# interface_a.net
KiCad netlist of a schematic drawn in EAGLE
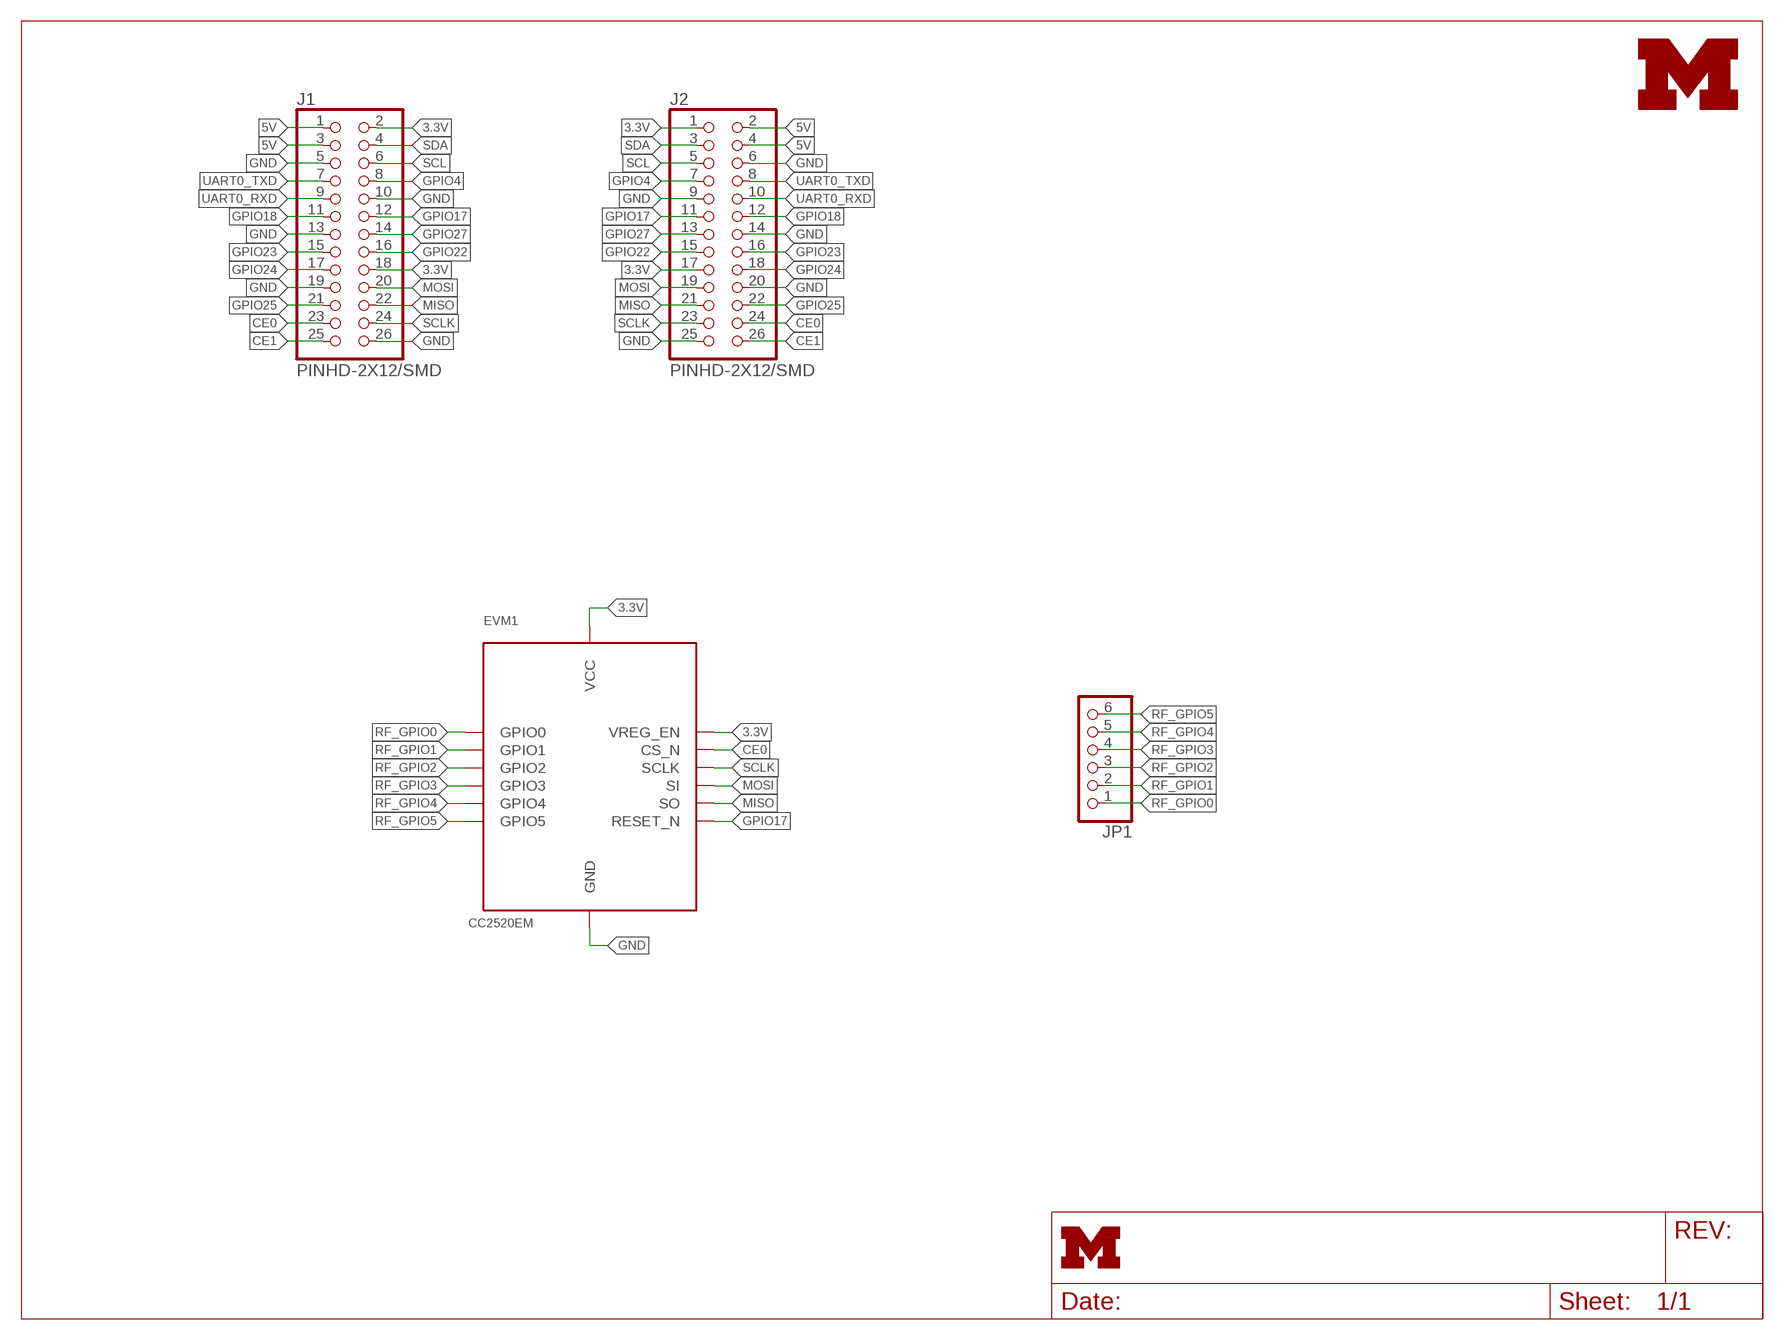
[diagram p0: schematic, sheet 1]

(export (version "E")
  (design (tool "Eeschema 10.0.6"))
  (components
    (comp (ref "EVM1")
      (value "CC2520EM")
      (footprint "eagle-import:TI_CC_EVM")
      (libsource (lib "eagle-import") (part "CC2520EM"))
    )
    (comp (ref "J1")
      (value "PINHD-2X12/SMD")
      (footprint "eagle-import:2X13_SMD")
      (libsource (lib "eagle-import") (part "PINHD-2X12/SMD"))
    )
    (comp (ref "J2")
      (value "PINHD-2X12/SMD")
      (footprint "eagle-import:2X13_SMD")
      (libsource (lib "eagle-import") (part "PINHD-2X12/SMD"))
    )
    (comp (ref "JP1")
      (value "PINHD-1X6/90")
      (footprint "eagle-import:1X06_90")
      (libsource (lib "eagle-import") (part "PINHD-1X6/90"))
    )
    (comp (ref "U$1")
      (value "UMICH_SOLID_SMALL")
      (footprint "eagle-import:UMICH_SOLID_75MIL")
      (libsource (lib "eagle-import") (part "UMICH_SOLID_SMALL"))
    )
  )
  (nets
    (net (code "1") (name "3.3V") (class "Default")
      (node (ref "EVM1") (pin "P1_10") (pinfunction "VREG_EN_P1_10") (pintype "bidirectional"))
      (node (ref "EVM1") (pin "P2_7") (pinfunction "VCC_P2_7") (pintype "bidirectional"))
      (node (ref "EVM1") (pin "P2_9") (pinfunction "VCC_P2_9") (pintype "bidirectional"))
      (node (ref "J1") (pin "18") (pinfunction "18_18") (pintype "passive"))
      (node (ref "J1") (pin "2") (pinfunction "2_2") (pintype "passive"))
      (node (ref "J2") (pin "1") (pinfunction "1_1") (pintype "passive"))
      (node (ref "J2") (pin "17") (pinfunction "17_17") (pintype "passive"))
    )
    (net (code "2") (name "5V") (class "Default")
      (node (ref "J1") (pin "1") (pinfunction "1_1") (pintype "passive"))
      (node (ref "J1") (pin "3") (pinfunction "3_3") (pintype "passive"))
      (node (ref "J2") (pin "2") (pinfunction "2_2") (pintype "passive"))
      (node (ref "J2") (pin "4") (pinfunction "4_4") (pintype "passive"))
    )
    (net (code "3") (name "CE0") (class "Default")
      (node (ref "EVM1") (pin "P1_14") (pinfunction "CS_N_P1_14") (pintype "bidirectional"))
      (node (ref "J1") (pin "23") (pinfunction "23_23") (pintype "passive"))
      (node (ref "J2") (pin "24") (pinfunction "24_24") (pintype "passive"))
    )
    (net (code "4") (name "CE1") (class "Default")
      (node (ref "J1") (pin "25") (pinfunction "25_25") (pintype "passive"))
      (node (ref "J2") (pin "26") (pinfunction "26_26") (pintype "passive"))
    )
    (net (code "5") (name "GND") (class "Default")
      (node (ref "EVM1") (pin "P1_1") (pinfunction "GND_P1_1") (pintype "bidirectional"))
      (node (ref "EVM1") (pin "P1_19") (pinfunction "GND_P1_19") (pintype "bidirectional"))
      (node (ref "J1") (pin "10") (pinfunction "10_10") (pintype "passive"))
      (node (ref "J1") (pin "13") (pinfunction "13_13") (pintype "passive"))
      (node (ref "J1") (pin "19") (pinfunction "19_19") (pintype "passive"))
      (node (ref "J1") (pin "26") (pinfunction "26_26") (pintype "passive"))
      (node (ref "J1") (pin "5") (pinfunction "5_5") (pintype "passive"))
      (node (ref "J2") (pin "14") (pinfunction "14_14") (pintype "passive"))
      (node (ref "J2") (pin "20") (pinfunction "20_20") (pintype "passive"))
      (node (ref "J2") (pin "25") (pinfunction "25_25") (pintype "passive"))
      (node (ref "J2") (pin "6") (pinfunction "6_6") (pintype "passive"))
      (node (ref "J2") (pin "9") (pinfunction "9_9") (pintype "passive"))
    )
    (net (code "6") (name "GPIO4") (class "Default")
      (node (ref "J1") (pin "8") (pinfunction "8_8") (pintype "passive"))
      (node (ref "J2") (pin "7") (pinfunction "7_7") (pintype "passive"))
    )
    (net (code "7") (name "GPIO17") (class "Default")
      (node (ref "EVM1") (pin "P2_15") (pinfunction "RESET_N_P2_15") (pintype "bidirectional"))
      (node (ref "J1") (pin "12") (pinfunction "12_12") (pintype "passive"))
      (node (ref "J2") (pin "11") (pinfunction "11_11") (pintype "passive"))
    )
    (net (code "8") (name "GPIO18") (class "Default")
      (node (ref "J1") (pin "11") (pinfunction "11_11") (pintype "passive"))
      (node (ref "J2") (pin "12") (pinfunction "12_12") (pintype "passive"))
    )
    (net (code "9") (name "GPIO22") (class "Default")
      (node (ref "J1") (pin "16") (pinfunction "16_16") (pintype "passive"))
      (node (ref "J2") (pin "15") (pinfunction "15_15") (pintype "passive"))
    )
    (net (code "10") (name "GPIO23") (class "Default")
      (node (ref "J1") (pin "15") (pinfunction "15_15") (pintype "passive"))
      (node (ref "J2") (pin "16") (pinfunction "16_16") (pintype "passive"))
    )
    (net (code "11") (name "GPIO24") (class "Default")
      (node (ref "J1") (pin "17") (pinfunction "17_17") (pintype "passive"))
      (node (ref "J2") (pin "18") (pinfunction "18_18") (pintype "passive"))
    )
    (net (code "12") (name "GPIO25") (class "Default")
      (node (ref "J1") (pin "21") (pinfunction "21_21") (pintype "passive"))
      (node (ref "J2") (pin "22") (pinfunction "22_22") (pintype "passive"))
    )
    (net (code "13") (name "GPIO27") (class "Default")
      (node (ref "J1") (pin "14") (pinfunction "14_14") (pintype "passive"))
      (node (ref "J2") (pin "13") (pinfunction "13_13") (pintype "passive"))
    )
    (net (code "14") (name "MISO") (class "Default")
      (node (ref "EVM1") (pin "P1_20") (pinfunction "SO_P1_20") (pintype "bidirectional"))
      (node (ref "J1") (pin "22") (pinfunction "22_22") (pintype "passive"))
      (node (ref "J2") (pin "21") (pinfunction "21_21") (pintype "passive"))
    )
    (net (code "15") (name "MOSI") (class "Default")
      (node (ref "EVM1") (pin "P1_18") (pinfunction "SI_P1_18") (pintype "bidirectional"))
      (node (ref "J1") (pin "20") (pinfunction "20_20") (pintype "passive"))
      (node (ref "J2") (pin "19") (pinfunction "19_19") (pintype "passive"))
    )
    (net (code "16") (name "RF_GPIO0") (class "Default")
      (node (ref "EVM1") (pin "P1_3") (pinfunction "GPIO0_P1_3") (pintype "bidirectional"))
      (node (ref "JP1") (pin "1") (pinfunction "1_1") (pintype "passive"))
    )
    (net (code "17") (name "RF_GPIO1") (class "Default")
      (node (ref "EVM1") (pin "P1_7") (pinfunction "GPIO1_P1_7") (pintype "bidirectional"))
      (node (ref "JP1") (pin "2") (pinfunction "2_2") (pintype "passive"))
    )
    (net (code "18") (name "RF_GPIO2") (class "Default")
      (node (ref "EVM1") (pin "P1_9") (pinfunction "GPIO2_P1_9") (pintype "bidirectional"))
      (node (ref "JP1") (pin "3") (pinfunction "3_3") (pintype "passive"))
    )
    (net (code "19") (name "RF_GPIO3") (class "Default")
      (node (ref "EVM1") (pin "P1_12") (pinfunction "GPIO3_P1_12") (pintype "bidirectional"))
      (node (ref "JP1") (pin "4") (pinfunction "4_4") (pintype "passive"))
    )
    (net (code "20") (name "RF_GPIO4") (class "Default")
      (node (ref "EVM1") (pin "P2_18") (pinfunction "GPIO4_P2_18") (pintype "bidirectional"))
      (node (ref "JP1") (pin "5") (pinfunction "5_5") (pintype "passive"))
    )
    (net (code "21") (name "RF_GPIO5") (class "Default")
      (node (ref "EVM1") (pin "P2_19") (pinfunction "GPIO5_P2_19") (pintype "bidirectional"))
      (node (ref "JP1") (pin "6") (pinfunction "6_6") (pintype "passive"))
    )
    (net (code "22") (name "SCL") (class "Default")
      (node (ref "J1") (pin "6") (pinfunction "6_6") (pintype "passive"))
      (node (ref "J2") (pin "5") (pinfunction "5_5") (pintype "passive"))
    )
    (net (code "23") (name "SCLK") (class "Default")
      (node (ref "EVM1") (pin "P1_16") (pinfunction "SCLK_P1_16") (pintype "bidirectional"))
      (node (ref "J1") (pin "24") (pinfunction "24_24") (pintype "passive"))
      (node (ref "J2") (pin "23") (pinfunction "23_23") (pintype "passive"))
    )
    (net (code "24") (name "SDA") (class "Default")
      (node (ref "J1") (pin "4") (pinfunction "4_4") (pintype "passive"))
      (node (ref "J2") (pin "3") (pinfunction "3_3") (pintype "passive"))
    )
    (net (code "25") (name "UART0_RXD") (class "Default")
      (node (ref "J1") (pin "9") (pinfunction "9_9") (pintype "passive"))
      (node (ref "J2") (pin "10") (pinfunction "10_10") (pintype "passive"))
    )
    (net (code "26") (name "UART0_TXD") (class "Default")
      (node (ref "J1") (pin "7") (pinfunction "7_7") (pintype "passive"))
      (node (ref "J2") (pin "8") (pinfunction "8_8") (pintype "passive"))
    )
  )
)
